# LED_OSRAM.net
KiCad netlist of a schematic drawn in Altium Designer
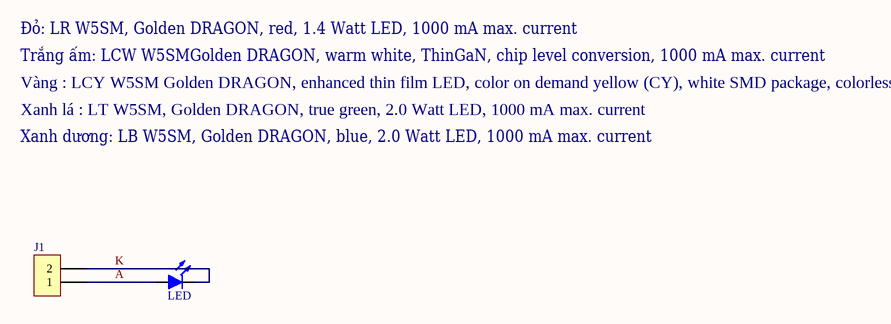
[diagram p0: LED OSRAM.SchDoc]

(export (version "E")
  (design (tool "Eeschema 10.0.6"))
  (components
    (comp (ref "J1")
      (value "Jump đực loại cong, 2 chân 2.54mm, hàn dán như bản vẽ")
      (footprint "LED OSRAM:HDR1x2")
      (libsource (lib "DnsSchLib") (part "CON2"))
    )
    (comp (ref "LED")
      (value "LED osram, hàn đúng mã, đúng cực, đáy LED dán silicon truyền nhiệt hoặc bôi keo tản nhiệt")
      (footprint "LED OSRAM:OSRAM_GOLDENDRAGON")
      (libsource (lib "swatpcblib") (part "Led"))
    )
  )
  (nets
    (net (code "1") (name "/A") (class "Default")
      (node (ref "J1") (pin "1") (pinfunction "1_1") (pintype "passive"))
      (node (ref "LED") (pin "A") (pinfunction "A_A") (pintype "passive"))
    )
    (net (code "2") (name "/K") (class "Default")
      (node (ref "J1") (pin "2") (pinfunction "2_2") (pintype "passive"))
      (node (ref "LED") (pin "K") (pinfunction "K_K") (pintype "passive"))
    )
  )
)
